# bigMama.net
KiCad netlist of a schematic drawn in Altium Designer
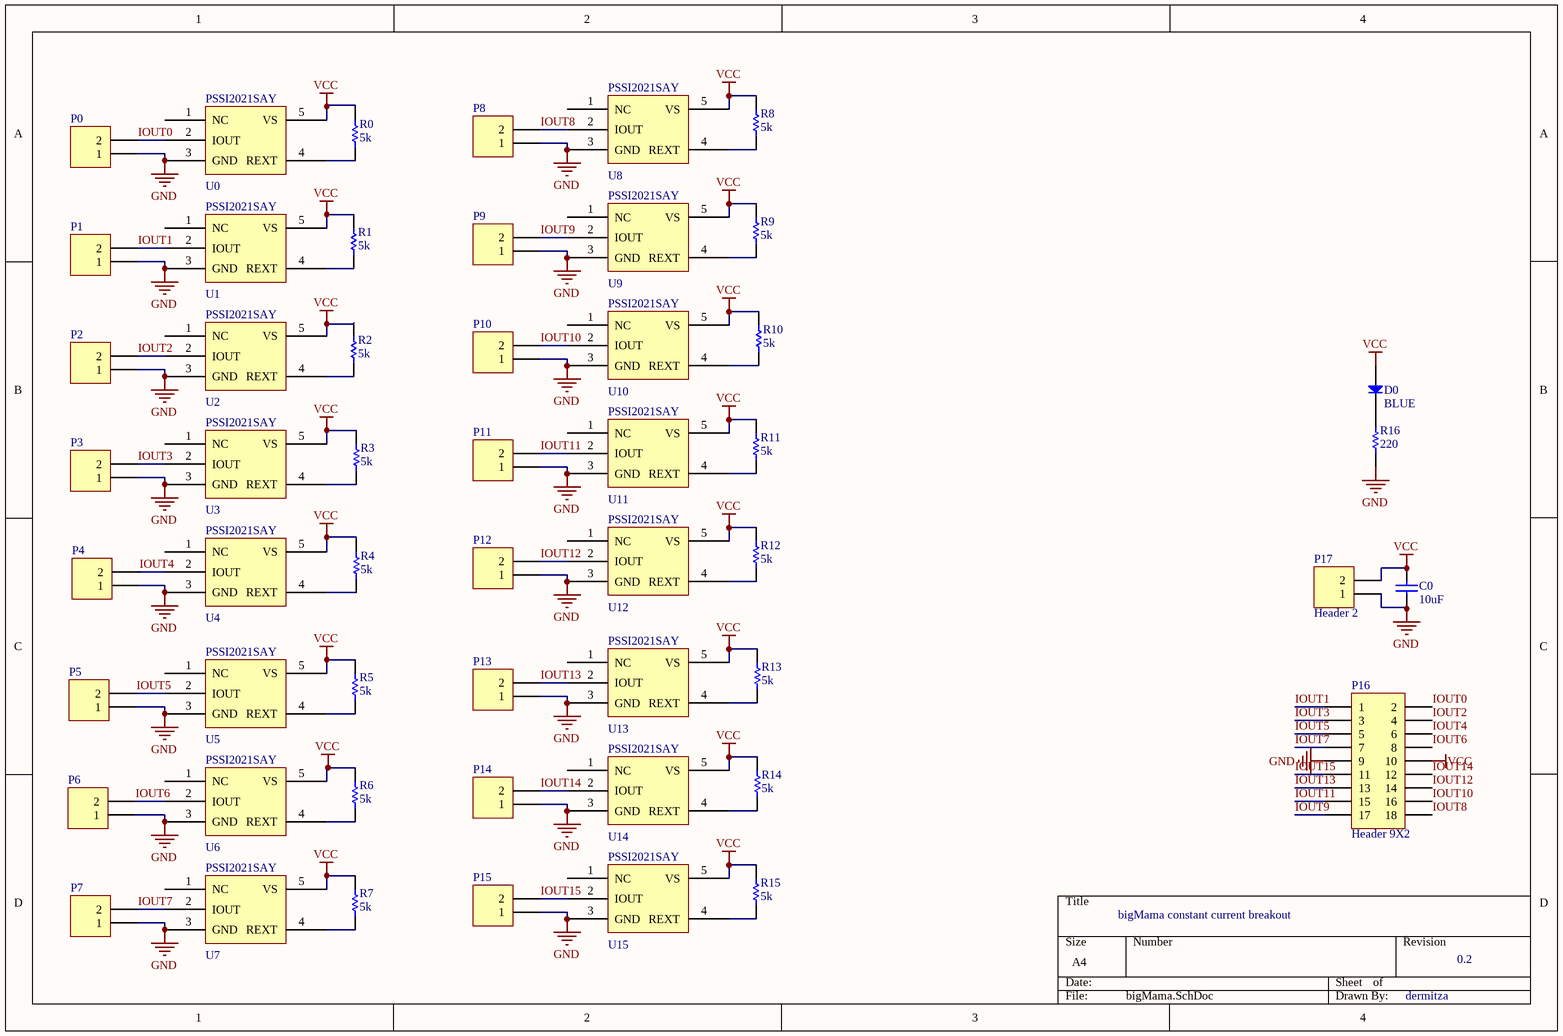
[diagram p0: bigMama.SchDoc]

(export (version "E")
  (design (tool "Eeschema 10.0.6"))
  (components
    (comp (ref "C0")
      (value "10uF")
      (footprint "0805_CAP")
      (description "Chip Capacitor")
      (libsource (lib "ailabLib") (part "CAP_SMD"))
    )
    (comp (ref "D0") (value "BLUE") (footprint "0603_LED") (libsource (lib "ailabLib") (part "LED_SMD")))
    (comp (ref "P0")
      (value "S0")
      (footprint "HDR1X2")
      (description "Header, 2-Pin")
      (fields (field (name "PUBLISHER") "Altium Limited"))
      (libsource (lib "Miscellaneous Connectors") (part "Header 2"))
    )
    (comp (ref "P1")
      (value "S0")
      (footprint "HDR1X2")
      (description "Header, 2-Pin")
      (fields (field (name "PUBLISHER") "Altium Limited"))
      (libsource (lib "Miscellaneous Connectors") (part "Header 2"))
    )
    (comp (ref "P2")
      (value "S0")
      (footprint "HDR1X2")
      (description "Header, 2-Pin")
      (fields (field (name "PUBLISHER") "Altium Limited"))
      (libsource (lib "Miscellaneous Connectors") (part "Header 2"))
    )
    (comp (ref "P3")
      (value "S0")
      (footprint "HDR1X2")
      (description "Header, 2-Pin")
      (fields (field (name "PUBLISHER") "Altium Limited"))
      (libsource (lib "Miscellaneous Connectors") (part "Header 2"))
    )
    (comp (ref "P4")
      (value "S0")
      (footprint "HDR1X2")
      (description "Header, 2-Pin")
      (fields (field (name "PUBLISHER") "Altium Limited"))
      (libsource (lib "Miscellaneous Connectors") (part "Header 2"))
    )
    (comp (ref "P5")
      (value "S0")
      (footprint "HDR1X2")
      (description "Header, 2-Pin")
      (fields (field (name "PUBLISHER") "Altium Limited"))
      (libsource (lib "Miscellaneous Connectors") (part "Header 2"))
    )
    (comp (ref "P6")
      (value "S0")
      (footprint "HDR1X2")
      (description "Header, 2-Pin")
      (fields (field (name "PUBLISHER") "Altium Limited"))
      (libsource (lib "Miscellaneous Connectors") (part "Header 2"))
    )
    (comp (ref "P7")
      (value "S0")
      (footprint "HDR1X2")
      (description "Header, 2-Pin")
      (fields (field (name "PUBLISHER") "Altium Limited"))
      (libsource (lib "Miscellaneous Connectors") (part "Header 2"))
    )
    (comp (ref "P8")
      (value "S0")
      (footprint "HDR1X2")
      (description "Header, 2-Pin")
      (fields (field (name "PUBLISHER") "Altium Limited"))
      (libsource (lib "Miscellaneous Connectors") (part "Header 2"))
    )
    (comp (ref "P9")
      (value "S0")
      (footprint "HDR1X2")
      (description "Header, 2-Pin")
      (fields (field (name "PUBLISHER") "Altium Limited"))
      (libsource (lib "Miscellaneous Connectors") (part "Header 2"))
    )
    (comp (ref "P10")
      (value "S0")
      (footprint "HDR1X2")
      (description "Header, 2-Pin")
      (fields (field (name "PUBLISHER") "Altium Limited"))
      (libsource (lib "Miscellaneous Connectors") (part "Header 2"))
    )
    (comp (ref "P11")
      (value "S0")
      (footprint "HDR1X2")
      (description "Header, 2-Pin")
      (fields (field (name "PUBLISHER") "Altium Limited"))
      (libsource (lib "Miscellaneous Connectors") (part "Header 2"))
    )
    (comp (ref "P12")
      (value "S0")
      (footprint "HDR1X2")
      (description "Header, 2-Pin")
      (fields (field (name "PUBLISHER") "Altium Limited"))
      (libsource (lib "Miscellaneous Connectors") (part "Header 2"))
    )
    (comp (ref "P13")
      (value "S0")
      (footprint "HDR1X2")
      (description "Header, 2-Pin")
      (fields (field (name "PUBLISHER") "Altium Limited"))
      (libsource (lib "Miscellaneous Connectors") (part "Header 2"))
    )
    (comp (ref "P14")
      (value "S0")
      (footprint "HDR1X2")
      (description "Header, 2-Pin")
      (fields (field (name "PUBLISHER") "Altium Limited"))
      (libsource (lib "Miscellaneous Connectors") (part "Header 2"))
    )
    (comp (ref "P15")
      (value "S0")
      (footprint "HDR1X2")
      (description "Header, 2-Pin")
      (fields (field (name "PUBLISHER") "Altium Limited"))
      (libsource (lib "Miscellaneous Connectors") (part "Header 2"))
    )
    (comp (ref "P16")
      (value "Header 9X2")
      (footprint "HDR2X9")
      (description "Header, 9-Pin, Dual row")
      (fields (field (name "PUBLISHER") "Altium Limited"))
      (libsource (lib "Miscellaneous Connectors") (part "Header 9X2"))
    )
    (comp (ref "P17")
      (value "Header 2")
      (footprint "HDR1X2")
      (description "Header, 2-Pin")
      (fields (field (name "PUBLISHER") "Altium Limited"))
      (libsource (lib "Miscellaneous Connectors") (part "Header 2"))
    )
    (comp (ref "R0") (value "5k") (footprint "0603_RES") (libsource (lib "ailabLib") (part "RES_SMD")))
    (comp (ref "R1") (value "5k") (footprint "0603_RES") (libsource (lib "ailabLib") (part "RES_SMD")))
    (comp (ref "R2") (value "5k") (footprint "0603_RES") (libsource (lib "ailabLib") (part "RES_SMD")))
    (comp (ref "R3") (value "5k") (footprint "0603_RES") (libsource (lib "ailabLib") (part "RES_SMD")))
    (comp (ref "R4") (value "5k") (footprint "0603_RES") (libsource (lib "ailabLib") (part "RES_SMD")))
    (comp (ref "R5") (value "5k") (footprint "0603_RES") (libsource (lib "ailabLib") (part "RES_SMD")))
    (comp (ref "R6") (value "5k") (footprint "0603_RES") (libsource (lib "ailabLib") (part "RES_SMD")))
    (comp (ref "R7") (value "5k") (footprint "0603_RES") (libsource (lib "ailabLib") (part "RES_SMD")))
    (comp (ref "R8") (value "5k") (footprint "0603_RES") (libsource (lib "ailabLib") (part "RES_SMD")))
    (comp (ref "R9") (value "5k") (footprint "0603_RES") (libsource (lib "ailabLib") (part "RES_SMD")))
    (comp (ref "R10") (value "5k") (footprint "0603_RES") (libsource (lib "ailabLib") (part "RES_SMD")))
    (comp (ref "R11") (value "5k") (footprint "0603_RES") (libsource (lib "ailabLib") (part "RES_SMD")))
    (comp (ref "R12") (value "5k") (footprint "0603_RES") (libsource (lib "ailabLib") (part "RES_SMD")))
    (comp (ref "R13") (value "5k") (footprint "0603_RES") (libsource (lib "ailabLib") (part "RES_SMD")))
    (comp (ref "R14") (value "5k") (footprint "0603_RES") (libsource (lib "ailabLib") (part "RES_SMD")))
    (comp (ref "R15") (value "5k") (footprint "0603_RES") (libsource (lib "ailabLib") (part "RES_SMD")))
    (comp (ref "R16") (value "220") (footprint "0603_RES") (libsource (lib "ailabLib") (part "RES_SMD")))
    (comp (ref "U0")
      (value "PSSI2021SAY")
      (footprint "SOT65P210X110-5N")
      (libsource (lib "ailabLib") (part "PSSI2021SAY"))
    )
    (comp (ref "U1")
      (value "PSSI2021SAY")
      (footprint "SOT65P210X110-5N")
      (libsource (lib "ailabLib") (part "PSSI2021SAY"))
    )
    (comp (ref "U2")
      (value "PSSI2021SAY")
      (footprint "SOT65P210X110-5N")
      (libsource (lib "ailabLib") (part "PSSI2021SAY"))
    )
    (comp (ref "U3")
      (value "PSSI2021SAY")
      (footprint "SOT65P210X110-5N")
      (libsource (lib "ailabLib") (part "PSSI2021SAY"))
    )
    (comp (ref "U4")
      (value "PSSI2021SAY")
      (footprint "SOT65P210X110-5N")
      (libsource (lib "ailabLib") (part "PSSI2021SAY"))
    )
    (comp (ref "U5")
      (value "PSSI2021SAY")
      (footprint "SOT65P210X110-5N")
      (libsource (lib "ailabLib") (part "PSSI2021SAY"))
    )
    (comp (ref "U6")
      (value "PSSI2021SAY")
      (footprint "SOT65P210X110-5N")
      (libsource (lib "ailabLib") (part "PSSI2021SAY"))
    )
    (comp (ref "U7")
      (value "PSSI2021SAY")
      (footprint "SOT65P210X110-5N")
      (libsource (lib "ailabLib") (part "PSSI2021SAY"))
    )
    (comp (ref "U8")
      (value "PSSI2021SAY")
      (footprint "SOT65P210X110-5N")
      (libsource (lib "ailabLib") (part "PSSI2021SAY"))
    )
    (comp (ref "U9")
      (value "PSSI2021SAY")
      (footprint "SOT65P210X110-5N")
      (libsource (lib "ailabLib") (part "PSSI2021SAY"))
    )
    (comp (ref "U10")
      (value "PSSI2021SAY")
      (footprint "SOT65P210X110-5N")
      (libsource (lib "ailabLib") (part "PSSI2021SAY"))
    )
    (comp (ref "U11")
      (value "PSSI2021SAY")
      (footprint "SOT65P210X110-5N")
      (libsource (lib "ailabLib") (part "PSSI2021SAY"))
    )
    (comp (ref "U12")
      (value "PSSI2021SAY")
      (footprint "SOT65P210X110-5N")
      (libsource (lib "ailabLib") (part "PSSI2021SAY"))
    )
    (comp (ref "U13")
      (value "PSSI2021SAY")
      (footprint "SOT65P210X110-5N")
      (libsource (lib "ailabLib") (part "PSSI2021SAY"))
    )
    (comp (ref "U14")
      (value "PSSI2021SAY")
      (footprint "SOT65P210X110-5N")
      (libsource (lib "ailabLib") (part "PSSI2021SAY"))
    )
    (comp (ref "U15")
      (value "PSSI2021SAY")
      (footprint "SOT65P210X110-5N")
      (libsource (lib "ailabLib") (part "PSSI2021SAY"))
    )
  )
  (nets
    (net (code "1") (name "/IOUT0") (class "Default")
      (node (ref "P0") (pin "2") (pinfunction "2_2") (pintype "passive"))
      (node (ref "P16") (pin "2") (pinfunction "2_2") (pintype "passive"))
      (node (ref "U0") (pin "2") (pinfunction "IOUT_2") (pintype "passive"))
    )
    (net (code "2") (name "/IOUT1") (class "Default")
      (node (ref "P1") (pin "2") (pinfunction "2_2") (pintype "passive"))
      (node (ref "P16") (pin "1") (pinfunction "1_1") (pintype "passive"))
      (node (ref "U1") (pin "2") (pinfunction "IOUT_2") (pintype "passive"))
    )
    (net (code "3") (name "/IOUT2") (class "Default")
      (node (ref "P16") (pin "4") (pinfunction "4_4") (pintype "passive"))
      (node (ref "P2") (pin "2") (pinfunction "2_2") (pintype "passive"))
      (node (ref "U2") (pin "2") (pinfunction "IOUT_2") (pintype "passive"))
    )
    (net (code "4") (name "/IOUT3") (class "Default")
      (node (ref "P16") (pin "3") (pinfunction "3_3") (pintype "passive"))
      (node (ref "P3") (pin "2") (pinfunction "2_2") (pintype "passive"))
      (node (ref "U3") (pin "2") (pinfunction "IOUT_2") (pintype "passive"))
    )
    (net (code "5") (name "/IOUT4") (class "Default")
      (node (ref "P16") (pin "6") (pinfunction "6_6") (pintype "passive"))
      (node (ref "P4") (pin "2") (pinfunction "2_2") (pintype "passive"))
      (node (ref "U4") (pin "2") (pinfunction "IOUT_2") (pintype "passive"))
    )
    (net (code "6") (name "/IOUT5") (class "Default")
      (node (ref "P16") (pin "5") (pinfunction "5_5") (pintype "passive"))
      (node (ref "P5") (pin "2") (pinfunction "2_2") (pintype "passive"))
      (node (ref "U5") (pin "2") (pinfunction "IOUT_2") (pintype "passive"))
    )
    (net (code "7") (name "/IOUT6") (class "Default")
      (node (ref "P16") (pin "8") (pinfunction "8_8") (pintype "passive"))
      (node (ref "P6") (pin "2") (pinfunction "2_2") (pintype "passive"))
      (node (ref "U6") (pin "2") (pinfunction "IOUT_2") (pintype "passive"))
    )
    (net (code "8") (name "/IOUT7") (class "Default")
      (node (ref "P16") (pin "7") (pinfunction "7_7") (pintype "passive"))
      (node (ref "P7") (pin "2") (pinfunction "2_2") (pintype "passive"))
      (node (ref "U7") (pin "2") (pinfunction "IOUT_2") (pintype "passive"))
    )
    (net (code "9") (name "/IOUT8") (class "Default")
      (node (ref "P16") (pin "18") (pinfunction "18_18") (pintype "passive"))
      (node (ref "P8") (pin "2") (pinfunction "2_2") (pintype "passive"))
      (node (ref "U8") (pin "2") (pinfunction "IOUT_2") (pintype "passive"))
    )
    (net (code "10") (name "/IOUT9") (class "Default")
      (node (ref "P16") (pin "17") (pinfunction "17_17") (pintype "passive"))
      (node (ref "P9") (pin "2") (pinfunction "2_2") (pintype "passive"))
      (node (ref "U9") (pin "2") (pinfunction "IOUT_2") (pintype "passive"))
    )
    (net (code "11") (name "/IOUT10") (class "Default")
      (node (ref "P10") (pin "2") (pinfunction "2_2") (pintype "passive"))
      (node (ref "P16") (pin "16") (pinfunction "16_16") (pintype "passive"))
      (node (ref "U10") (pin "2") (pinfunction "IOUT_2") (pintype "passive"))
    )
    (net (code "12") (name "/IOUT11") (class "Default")
      (node (ref "P11") (pin "2") (pinfunction "2_2") (pintype "passive"))
      (node (ref "P16") (pin "15") (pinfunction "15_15") (pintype "passive"))
      (node (ref "U11") (pin "2") (pinfunction "IOUT_2") (pintype "passive"))
    )
    (net (code "13") (name "/IOUT12") (class "Default")
      (node (ref "P12") (pin "2") (pinfunction "2_2") (pintype "passive"))
      (node (ref "P16") (pin "14") (pinfunction "14_14") (pintype "passive"))
      (node (ref "U12") (pin "2") (pinfunction "IOUT_2") (pintype "passive"))
    )
    (net (code "14") (name "/IOUT13") (class "Default")
      (node (ref "P13") (pin "2") (pinfunction "2_2") (pintype "passive"))
      (node (ref "P16") (pin "13") (pinfunction "13_13") (pintype "passive"))
      (node (ref "U13") (pin "2") (pinfunction "IOUT_2") (pintype "passive"))
    )
    (net (code "15") (name "/IOUT14") (class "Default")
      (node (ref "P14") (pin "2") (pinfunction "2_2") (pintype "passive"))
      (node (ref "P16") (pin "12") (pinfunction "12_12") (pintype "passive"))
      (node (ref "U14") (pin "2") (pinfunction "IOUT_2") (pintype "passive"))
    )
    (net (code "16") (name "/IOUT15") (class "Default")
      (node (ref "P15") (pin "2") (pinfunction "2_2") (pintype "passive"))
      (node (ref "P16") (pin "11") (pinfunction "11_11") (pintype "passive"))
      (node (ref "U15") (pin "2") (pinfunction "IOUT_2") (pintype "passive"))
    )
    (net (code "17") (name "GND") (class "Default")
      (node (ref "C0") (pin "1") (pinfunction "1_1") (pintype "passive"))
      (node (ref "P0") (pin "1") (pinfunction "1_1") (pintype "passive"))
      (node (ref "P1") (pin "1") (pinfunction "1_1") (pintype "passive"))
      (node (ref "P10") (pin "1") (pinfunction "1_1") (pintype "passive"))
      (node (ref "P11") (pin "1") (pinfunction "1_1") (pintype "passive"))
      (node (ref "P12") (pin "1") (pinfunction "1_1") (pintype "passive"))
      (node (ref "P13") (pin "1") (pinfunction "1_1") (pintype "passive"))
      (node (ref "P14") (pin "1") (pinfunction "1_1") (pintype "passive"))
      (node (ref "P15") (pin "1") (pinfunction "1_1") (pintype "passive"))
      (node (ref "P16") (pin "9") (pinfunction "9_9") (pintype "passive"))
      (node (ref "P17") (pin "1") (pinfunction "1_1") (pintype "passive"))
      (node (ref "P2") (pin "1") (pinfunction "1_1") (pintype "passive"))
      (node (ref "P3") (pin "1") (pinfunction "1_1") (pintype "passive"))
      (node (ref "P4") (pin "1") (pinfunction "1_1") (pintype "passive"))
      (node (ref "P5") (pin "1") (pinfunction "1_1") (pintype "passive"))
      (node (ref "P6") (pin "1") (pinfunction "1_1") (pintype "passive"))
      (node (ref "P7") (pin "1") (pinfunction "1_1") (pintype "passive"))
      (node (ref "P8") (pin "1") (pinfunction "1_1") (pintype "passive"))
      (node (ref "P9") (pin "1") (pinfunction "1_1") (pintype "passive"))
      (node (ref "R16") (pin "1") (pinfunction "1_1") (pintype "passive"))
      (node (ref "U0") (pin "3") (pinfunction "GND_3") (pintype "passive"))
      (node (ref "U1") (pin "3") (pinfunction "GND_3") (pintype "passive"))
      (node (ref "U10") (pin "3") (pinfunction "GND_3") (pintype "passive"))
      (node (ref "U11") (pin "3") (pinfunction "GND_3") (pintype "passive"))
      (node (ref "U12") (pin "3") (pinfunction "GND_3") (pintype "passive"))
      (node (ref "U13") (pin "3") (pinfunction "GND_3") (pintype "passive"))
      (node (ref "U14") (pin "3") (pinfunction "GND_3") (pintype "passive"))
      (node (ref "U15") (pin "3") (pinfunction "GND_3") (pintype "passive"))
      (node (ref "U2") (pin "3") (pinfunction "GND_3") (pintype "passive"))
      (node (ref "U3") (pin "3") (pinfunction "GND_3") (pintype "passive"))
      (node (ref "U4") (pin "3") (pinfunction "GND_3") (pintype "passive"))
      (node (ref "U5") (pin "3") (pinfunction "GND_3") (pintype "passive"))
      (node (ref "U6") (pin "3") (pinfunction "GND_3") (pintype "passive"))
      (node (ref "U7") (pin "3") (pinfunction "GND_3") (pintype "passive"))
      (node (ref "U8") (pin "3") (pinfunction "GND_3") (pintype "passive"))
      (node (ref "U9") (pin "3") (pinfunction "GND_3") (pintype "passive"))
    )
    (net (code "18") (name "Net-(D0-K)") (class "Default")
      (node (ref "D0") (pin "2") (pinfunction "K_2") (pintype "passive"))
      (node (ref "R16") (pin "2") (pinfunction "2_2") (pintype "passive"))
    )
    (net (code "19") (name "Net-(U0-REXT)") (class "Default")
      (node (ref "R0") (pin "1") (pinfunction "1_1") (pintype "passive"))
      (node (ref "U0") (pin "4") (pinfunction "REXT_4") (pintype "passive"))
    )
    (net (code "20") (name "Net-(U1-REXT)") (class "Default")
      (node (ref "R1") (pin "1") (pinfunction "1_1") (pintype "passive"))
      (node (ref "U1") (pin "4") (pinfunction "REXT_4") (pintype "passive"))
    )
    (net (code "21") (name "Net-(U2-REXT)") (class "Default")
      (node (ref "R2") (pin "1") (pinfunction "1_1") (pintype "passive"))
      (node (ref "U2") (pin "4") (pinfunction "REXT_4") (pintype "passive"))
    )
    (net (code "22") (name "Net-(U3-REXT)") (class "Default")
      (node (ref "R3") (pin "1") (pinfunction "1_1") (pintype "passive"))
      (node (ref "U3") (pin "4") (pinfunction "REXT_4") (pintype "passive"))
    )
    (net (code "23") (name "Net-(U4-REXT)") (class "Default")
      (node (ref "R4") (pin "1") (pinfunction "1_1") (pintype "passive"))
      (node (ref "U4") (pin "4") (pinfunction "REXT_4") (pintype "passive"))
    )
    (net (code "24") (name "Net-(U5-REXT)") (class "Default")
      (node (ref "R5") (pin "1") (pinfunction "1_1") (pintype "passive"))
      (node (ref "U5") (pin "4") (pinfunction "REXT_4") (pintype "passive"))
    )
    (net (code "25") (name "Net-(U6-REXT)") (class "Default")
      (node (ref "R6") (pin "1") (pinfunction "1_1") (pintype "passive"))
      (node (ref "U6") (pin "4") (pinfunction "REXT_4") (pintype "passive"))
    )
    (net (code "26") (name "Net-(U7-REXT)") (class "Default")
      (node (ref "R7") (pin "1") (pinfunction "1_1") (pintype "passive"))
      (node (ref "U7") (pin "4") (pinfunction "REXT_4") (pintype "passive"))
    )
    (net (code "27") (name "Net-(U8-REXT)") (class "Default")
      (node (ref "R8") (pin "1") (pinfunction "1_1") (pintype "passive"))
      (node (ref "U8") (pin "4") (pinfunction "REXT_4") (pintype "passive"))
    )
    (net (code "28") (name "Net-(U9-REXT)") (class "Default")
      (node (ref "R9") (pin "1") (pinfunction "1_1") (pintype "passive"))
      (node (ref "U9") (pin "4") (pinfunction "REXT_4") (pintype "passive"))
    )
    (net (code "29") (name "Net-(U10-REXT)") (class "Default")
      (node (ref "R10") (pin "1") (pinfunction "1_1") (pintype "passive"))
      (node (ref "U10") (pin "4") (pinfunction "REXT_4") (pintype "passive"))
    )
    (net (code "30") (name "Net-(U11-REXT)") (class "Default")
      (node (ref "R11") (pin "1") (pinfunction "1_1") (pintype "passive"))
      (node (ref "U11") (pin "4") (pinfunction "REXT_4") (pintype "passive"))
    )
    (net (code "31") (name "Net-(U12-REXT)") (class "Default")
      (node (ref "R12") (pin "1") (pinfunction "1_1") (pintype "passive"))
      (node (ref "U12") (pin "4") (pinfunction "REXT_4") (pintype "passive"))
    )
    (net (code "32") (name "Net-(U13-REXT)") (class "Default")
      (node (ref "R13") (pin "1") (pinfunction "1_1") (pintype "passive"))
      (node (ref "U13") (pin "4") (pinfunction "REXT_4") (pintype "passive"))
    )
    (net (code "33") (name "Net-(U14-REXT)") (class "Default")
      (node (ref "R14") (pin "1") (pinfunction "1_1") (pintype "passive"))
      (node (ref "U14") (pin "4") (pinfunction "REXT_4") (pintype "passive"))
    )
    (net (code "34") (name "Net-(U15-REXT)") (class "Default")
      (node (ref "R15") (pin "1") (pinfunction "1_1") (pintype "passive"))
      (node (ref "U15") (pin "4") (pinfunction "REXT_4") (pintype "passive"))
    )
    (net (code "35") (name "VCC") (class "Default")
      (node (ref "C0") (pin "2") (pinfunction "2_2") (pintype "passive"))
      (node (ref "D0") (pin "1") (pinfunction "A_1") (pintype "passive"))
      (node (ref "P16") (pin "10") (pinfunction "10_10") (pintype "passive"))
      (node (ref "P17") (pin "2") (pinfunction "2_2") (pintype "passive"))
      (node (ref "R0") (pin "2") (pinfunction "2_2") (pintype "passive"))
      (node (ref "R1") (pin "2") (pinfunction "2_2") (pintype "passive"))
      (node (ref "R10") (pin "2") (pinfunction "2_2") (pintype "passive"))
      (node (ref "R11") (pin "2") (pinfunction "2_2") (pintype "passive"))
      (node (ref "R12") (pin "2") (pinfunction "2_2") (pintype "passive"))
      (node (ref "R13") (pin "2") (pinfunction "2_2") (pintype "passive"))
      (node (ref "R14") (pin "2") (pinfunction "2_2") (pintype "passive"))
      (node (ref "R15") (pin "2") (pinfunction "2_2") (pintype "passive"))
      (node (ref "R2") (pin "2") (pinfunction "2_2") (pintype "passive"))
      (node (ref "R3") (pin "2") (pinfunction "2_2") (pintype "passive"))
      (node (ref "R4") (pin "2") (pinfunction "2_2") (pintype "passive"))
      (node (ref "R5") (pin "2") (pinfunction "2_2") (pintype "passive"))
      (node (ref "R6") (pin "2") (pinfunction "2_2") (pintype "passive"))
      (node (ref "R7") (pin "2") (pinfunction "2_2") (pintype "passive"))
      (node (ref "R8") (pin "2") (pinfunction "2_2") (pintype "passive"))
      (node (ref "R9") (pin "2") (pinfunction "2_2") (pintype "passive"))
      (node (ref "U0") (pin "5") (pinfunction "VS_5") (pintype "passive"))
      (node (ref "U1") (pin "5") (pinfunction "VS_5") (pintype "passive"))
      (node (ref "U10") (pin "5") (pinfunction "VS_5") (pintype "passive"))
      (node (ref "U11") (pin "5") (pinfunction "VS_5") (pintype "passive"))
      (node (ref "U12") (pin "5") (pinfunction "VS_5") (pintype "passive"))
      (node (ref "U13") (pin "5") (pinfunction "VS_5") (pintype "passive"))
      (node (ref "U14") (pin "5") (pinfunction "VS_5") (pintype "passive"))
      (node (ref "U15") (pin "5") (pinfunction "VS_5") (pintype "passive"))
      (node (ref "U2") (pin "5") (pinfunction "VS_5") (pintype "passive"))
      (node (ref "U3") (pin "5") (pinfunction "VS_5") (pintype "passive"))
      (node (ref "U4") (pin "5") (pinfunction "VS_5") (pintype "passive"))
      (node (ref "U5") (pin "5") (pinfunction "VS_5") (pintype "passive"))
      (node (ref "U6") (pin "5") (pinfunction "VS_5") (pintype "passive"))
      (node (ref "U7") (pin "5") (pinfunction "VS_5") (pintype "passive"))
      (node (ref "U8") (pin "5") (pinfunction "VS_5") (pintype "passive"))
      (node (ref "U9") (pin "5") (pinfunction "VS_5") (pintype "passive"))
    )
    (net (code "36") (name "unconnected-(U0-NC-Pad1)") (class "Default")
      (node (ref "U0") (pin "1") (pinfunction "NC_1") (pintype "passive"))
    )
    (net (code "37") (name "unconnected-(U1-NC-Pad1)") (class "Default")
      (node (ref "U1") (pin "1") (pinfunction "NC_1") (pintype "passive"))
    )
    (net (code "38") (name "unconnected-(U2-NC-Pad1)") (class "Default")
      (node (ref "U2") (pin "1") (pinfunction "NC_1") (pintype "passive"))
    )
    (net (code "39") (name "unconnected-(U3-NC-Pad1)") (class "Default")
      (node (ref "U3") (pin "1") (pinfunction "NC_1") (pintype "passive"))
    )
    (net (code "40") (name "unconnected-(U4-NC-Pad1)") (class "Default")
      (node (ref "U4") (pin "1") (pinfunction "NC_1") (pintype "passive"))
    )
    (net (code "41") (name "unconnected-(U5-NC-Pad1)") (class "Default")
      (node (ref "U5") (pin "1") (pinfunction "NC_1") (pintype "passive"))
    )
    (net (code "42") (name "unconnected-(U6-NC-Pad1)") (class "Default")
      (node (ref "U6") (pin "1") (pinfunction "NC_1") (pintype "passive"))
    )
    (net (code "43") (name "unconnected-(U7-NC-Pad1)") (class "Default")
      (node (ref "U7") (pin "1") (pinfunction "NC_1") (pintype "passive"))
    )
    (net (code "44") (name "unconnected-(U8-NC-Pad1)") (class "Default")
      (node (ref "U8") (pin "1") (pinfunction "NC_1") (pintype "passive"))
    )
    (net (code "45") (name "unconnected-(U9-NC-Pad1)") (class "Default")
      (node (ref "U9") (pin "1") (pinfunction "NC_1") (pintype "passive"))
    )
    (net (code "46") (name "unconnected-(U10-NC-Pad1)") (class "Default")
      (node (ref "U10") (pin "1") (pinfunction "NC_1") (pintype "passive"))
    )
    (net (code "47") (name "unconnected-(U11-NC-Pad1)") (class "Default")
      (node (ref "U11") (pin "1") (pinfunction "NC_1") (pintype "passive"))
    )
    (net (code "48") (name "unconnected-(U12-NC-Pad1)") (class "Default")
      (node (ref "U12") (pin "1") (pinfunction "NC_1") (pintype "passive"))
    )
    (net (code "49") (name "unconnected-(U13-NC-Pad1)") (class "Default")
      (node (ref "U13") (pin "1") (pinfunction "NC_1") (pintype "passive"))
    )
    (net (code "50") (name "unconnected-(U14-NC-Pad1)") (class "Default")
      (node (ref "U14") (pin "1") (pinfunction "NC_1") (pintype "passive"))
    )
    (net (code "51") (name "unconnected-(U15-NC-Pad1)") (class "Default")
      (node (ref "U15") (pin "1") (pinfunction "NC_1") (pintype "passive"))
    )
  )
)
